# blimp_v1_-_modified.net
KiCad netlist of a schematic drawn in EAGLE
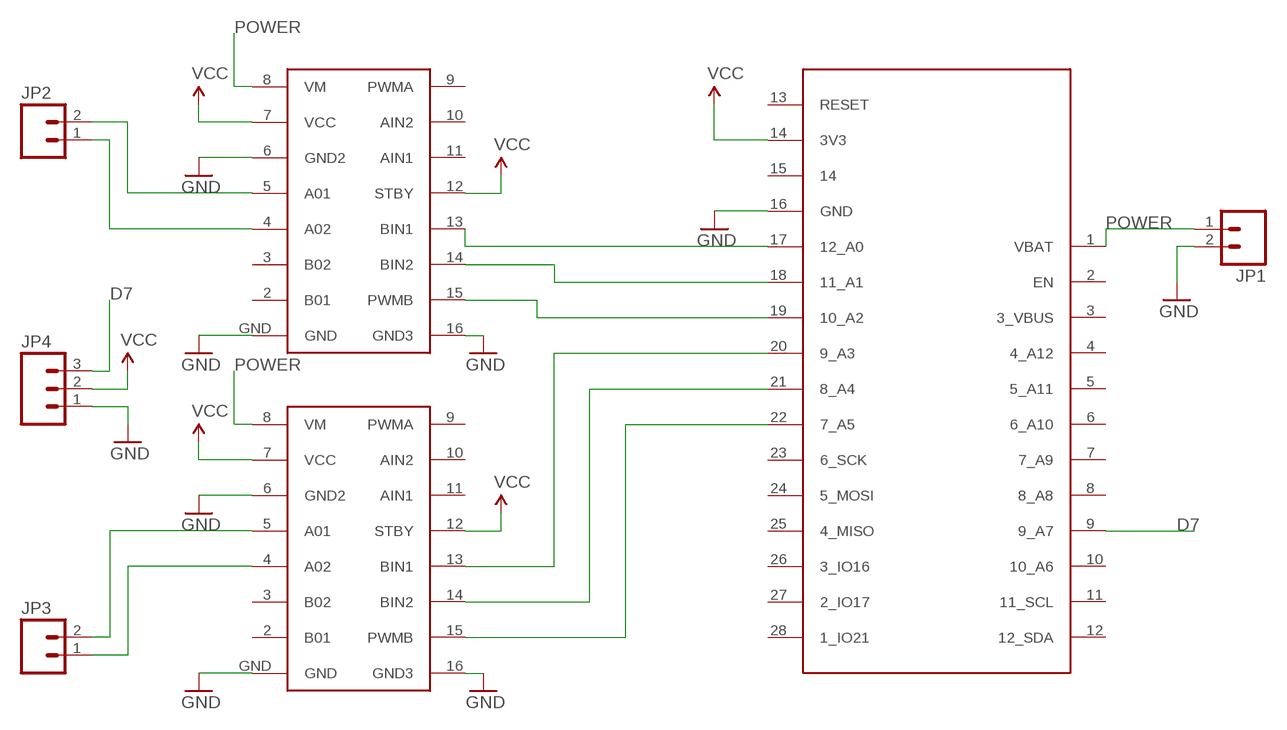
[diagram p0: schematic, sheet 1]

(export (version "E")
  (design (tool "Eeschema 10.0.6"))
  (components
    (comp (ref "JP1")
      (value "M02-JST-2MM-SMT")
      (footprint "eagle-import:JST-2-SMD")
      (libsource (lib "eagle-import") (part "M02-JST-2MM-SMT"))
    )
    (comp (ref "JP2")
      (value "M02PTH")
      (footprint "eagle-import:1X02")
      (libsource (lib "eagle-import") (part "M02PTH"))
    )
    (comp (ref "JP3")
      (value "M02PTH")
      (footprint "eagle-import:1X02")
      (libsource (lib "eagle-import") (part "M02PTH"))
    )
    (comp (ref "JP4")
      (value "M03PTH")
      (footprint "eagle-import:1X03")
      (libsource (lib "eagle-import") (part "M03PTH"))
    )
    (comp (ref "U$1")
      (value "ESP32")
      (footprint "eagle-import:ESP32")
      (libsource (lib "eagle-import") (part "ESP32"))
    )
    (comp (ref "U$2")
      (value "TB6612")
      (footprint "eagle-import:TB6612")
      (libsource (lib "eagle-import") (part "TB6612"))
    )
    (comp (ref "U$4")
      (value "TB6612")
      (footprint "eagle-import:TB6612")
      (libsource (lib "eagle-import") (part "TB6612"))
    )
  )
  (nets
    (net (code "1") (name "/D7") (class "Default")
      (node (ref "JP4") (pin "3") (pinfunction "3_3") (pintype "passive"))
      (node (ref "U$1") (pin "9") (pinfunction "9_A7_9") (pintype "bidirectional"))
    )
    (net (code "2") (name "/POWER") (class "Default")
      (node (ref "JP1") (pin "1") (pinfunction "1_1") (pintype "passive"))
      (node (ref "U$1") (pin "1") (pinfunction "VBAT_1") (pintype "bidirectional"))
      (node (ref "U$2") (pin "8") (pinfunction "VM_8") (pintype "bidirectional"))
      (node (ref "U$4") (pin "8") (pinfunction "VM_8") (pintype "bidirectional"))
    )
    (net (code "3") (name "GND") (class "Default")
      (node (ref "JP1") (pin "2") (pinfunction "2_2") (pintype "passive"))
      (node (ref "JP4") (pin "1") (pinfunction "1_1") (pintype "passive"))
      (node (ref "U$1") (pin "16") (pinfunction "GND_16") (pintype "bidirectional"))
      (node (ref "U$2") (pin "16") (pinfunction "GND3_16") (pintype "bidirectional"))
      (node (ref "U$2") (pin "6") (pinfunction "GND2_6") (pintype "bidirectional"))
      (node (ref "U$2") (pin "GND") (pinfunction "GND_GND") (pintype "bidirectional"))
      (node (ref "U$4") (pin "16") (pinfunction "GND3_16") (pintype "bidirectional"))
      (node (ref "U$4") (pin "6") (pinfunction "GND2_6") (pintype "bidirectional"))
      (node (ref "U$4") (pin "GND") (pinfunction "GND_GND") (pintype "bidirectional"))
    )
    (net (code "4") (name "Net-(U$1-7_A5)") (class "Default")
      (node (ref "U$1") (pin "22") (pinfunction "7_A5_22") (pintype "bidirectional"))
      (node (ref "U$2") (pin "15") (pinfunction "PWMB_15") (pintype "bidirectional"))
    )
    (net (code "5") (name "Net-(U$1-8_A4)") (class "Default")
      (node (ref "U$1") (pin "21") (pinfunction "8_A4_21") (pintype "bidirectional"))
      (node (ref "U$2") (pin "14") (pinfunction "BIN2_14") (pintype "bidirectional"))
    )
    (net (code "6") (name "Net-(U$1-9_A3)") (class "Default")
      (node (ref "U$1") (pin "20") (pinfunction "9_A3_20") (pintype "bidirectional"))
      (node (ref "U$2") (pin "13") (pinfunction "BIN1_13") (pintype "bidirectional"))
    )
    (net (code "7") (name "Net-(U$1-10_A2)") (class "Default")
      (node (ref "U$1") (pin "19") (pinfunction "10_A2_19") (pintype "bidirectional"))
      (node (ref "U$4") (pin "15") (pinfunction "PWMB_15") (pintype "bidirectional"))
    )
    (net (code "8") (name "Net-(U$1-11_A1)") (class "Default")
      (node (ref "U$1") (pin "18") (pinfunction "11_A1_18") (pintype "bidirectional"))
      (node (ref "U$4") (pin "14") (pinfunction "BIN2_14") (pintype "bidirectional"))
    )
    (net (code "9") (name "Net-(U$1-12_A0)") (class "Default")
      (node (ref "U$1") (pin "17") (pinfunction "12_A0_17") (pintype "bidirectional"))
      (node (ref "U$4") (pin "13") (pinfunction "BIN1_13") (pintype "bidirectional"))
    )
    (net (code "10") (name "Net-(U$2-A01)") (class "Default")
      (node (ref "JP3") (pin "2") (pinfunction "2_2") (pintype "passive"))
      (node (ref "U$2") (pin "5") (pinfunction "A01_5") (pintype "bidirectional"))
    )
    (net (code "11") (name "Net-(U$2-A02)") (class "Default")
      (node (ref "JP3") (pin "1") (pinfunction "1_1") (pintype "passive"))
      (node (ref "U$2") (pin "4") (pinfunction "A02_4") (pintype "bidirectional"))
    )
    (net (code "12") (name "Net-(U$4-A01)") (class "Default")
      (node (ref "JP2") (pin "2") (pinfunction "2_2") (pintype "passive"))
      (node (ref "U$4") (pin "5") (pinfunction "A01_5") (pintype "bidirectional"))
    )
    (net (code "13") (name "Net-(U$4-A02)") (class "Default")
      (node (ref "JP2") (pin "1") (pinfunction "1_1") (pintype "passive"))
      (node (ref "U$4") (pin "4") (pinfunction "A02_4") (pintype "bidirectional"))
    )
    (net (code "14") (name "VCC") (class "Default")
      (node (ref "JP4") (pin "2") (pinfunction "2_2") (pintype "passive"))
      (node (ref "U$1") (pin "14") (pinfunction "3V3_14") (pintype "bidirectional"))
      (node (ref "U$2") (pin "12") (pinfunction "STBY_12") (pintype "bidirectional"))
      (node (ref "U$2") (pin "7") (pinfunction "VCC_7") (pintype "bidirectional"))
      (node (ref "U$4") (pin "12") (pinfunction "STBY_12") (pintype "bidirectional"))
      (node (ref "U$4") (pin "7") (pinfunction "VCC_7") (pintype "bidirectional"))
    )
    (net (code "15") (name "unconnected-(U$1-1_IO21-Pad28)") (class "Default")
      (node (ref "U$1") (pin "28") (pinfunction "1_IO21_28") (pintype "bidirectional"))
    )
    (net (code "16") (name "unconnected-(U$1-2_IO17-Pad27)") (class "Default")
      (node (ref "U$1") (pin "27") (pinfunction "2_IO17_27") (pintype "bidirectional"))
    )
    (net (code "17") (name "unconnected-(U$1-3_IO16-Pad26)") (class "Default")
      (node (ref "U$1") (pin "26") (pinfunction "3_IO16_26") (pintype "bidirectional"))
    )
    (net (code "18") (name "unconnected-(U$1-3_VBUS-Pad3)") (class "Default")
      (node (ref "U$1") (pin "3") (pinfunction "3_VBUS_3") (pintype "bidirectional"))
    )
    (net (code "19") (name "unconnected-(U$1-4_A12-Pad4)") (class "Default")
      (node (ref "U$1") (pin "4") (pinfunction "4_A12_4") (pintype "bidirectional"))
    )
    (net (code "20") (name "unconnected-(U$1-4_MISO-Pad25)") (class "Default")
      (node (ref "U$1") (pin "25") (pinfunction "4_MISO_25") (pintype "bidirectional"))
    )
    (net (code "21") (name "unconnected-(U$1-5_A11-Pad5)") (class "Default")
      (node (ref "U$1") (pin "5") (pinfunction "5_A11_5") (pintype "bidirectional"))
    )
    (net (code "22") (name "unconnected-(U$1-5_MOSI-Pad24)") (class "Default")
      (node (ref "U$1") (pin "24") (pinfunction "5_MOSI_24") (pintype "bidirectional"))
    )
    (net (code "23") (name "unconnected-(U$1-6_A10-Pad6)") (class "Default")
      (node (ref "U$1") (pin "6") (pinfunction "6_A10_6") (pintype "bidirectional"))
    )
    (net (code "24") (name "unconnected-(U$1-6_SCK-Pad23)") (class "Default")
      (node (ref "U$1") (pin "23") (pinfunction "6_SCK_23") (pintype "bidirectional"))
    )
    (net (code "25") (name "unconnected-(U$1-7_A9-Pad7)") (class "Default")
      (node (ref "U$1") (pin "7") (pinfunction "7_A9_7") (pintype "bidirectional"))
    )
    (net (code "26") (name "unconnected-(U$1-8_A8-Pad8)") (class "Default")
      (node (ref "U$1") (pin "8") (pinfunction "8_A8_8") (pintype "bidirectional"))
    )
    (net (code "27") (name "unconnected-(U$1-10_A6-Pad10)") (class "Default")
      (node (ref "U$1") (pin "10") (pinfunction "10_A6_10") (pintype "bidirectional"))
    )
    (net (code "28") (name "unconnected-(U$1-11_SCL-Pad11)") (class "Default")
      (node (ref "U$1") (pin "11") (pinfunction "11_SCL_11") (pintype "bidirectional"))
    )
    (net (code "29") (name "unconnected-(U$1-12_SDA-Pad12)") (class "Default")
      (node (ref "U$1") (pin "12") (pinfunction "12_SDA_12") (pintype "bidirectional"))
    )
    (net (code "30") (name "unconnected-(U$1-14-Pad15)") (class "Default")
      (node (ref "U$1") (pin "15") (pinfunction "14_15") (pintype "bidirectional"))
    )
    (net (code "31") (name "unconnected-(U$1-EN-Pad2)") (class "Default")
      (node (ref "U$1") (pin "2") (pinfunction "EN_2") (pintype "bidirectional"))
    )
    (net (code "32") (name "unconnected-(U$1-RESET-Pad13)") (class "Default")
      (node (ref "U$1") (pin "13") (pinfunction "RESET_13") (pintype "bidirectional"))
    )
    (net (code "33") (name "unconnected-(U$2-AIN1-Pad11)") (class "Default")
      (node (ref "U$2") (pin "11") (pinfunction "AIN1_11") (pintype "bidirectional"))
    )
    (net (code "34") (name "unconnected-(U$2-AIN2-Pad10)") (class "Default")
      (node (ref "U$2") (pin "10") (pinfunction "AIN2_10") (pintype "bidirectional"))
    )
    (net (code "35") (name "unconnected-(U$2-B01-Pad2)") (class "Default")
      (node (ref "U$2") (pin "2") (pinfunction "B01_2") (pintype "bidirectional"))
    )
    (net (code "36") (name "unconnected-(U$2-B02-Pad3)") (class "Default")
      (node (ref "U$2") (pin "3") (pinfunction "B02_3") (pintype "bidirectional"))
    )
    (net (code "37") (name "unconnected-(U$2-PWMA-Pad9)") (class "Default")
      (node (ref "U$2") (pin "9") (pinfunction "PWMA_9") (pintype "bidirectional"))
    )
    (net (code "38") (name "unconnected-(U$4-AIN1-Pad11)") (class "Default")
      (node (ref "U$4") (pin "11") (pinfunction "AIN1_11") (pintype "bidirectional"))
    )
    (net (code "39") (name "unconnected-(U$4-AIN2-Pad10)") (class "Default")
      (node (ref "U$4") (pin "10") (pinfunction "AIN2_10") (pintype "bidirectional"))
    )
    (net (code "40") (name "unconnected-(U$4-B01-Pad2)") (class "Default")
      (node (ref "U$4") (pin "2") (pinfunction "B01_2") (pintype "bidirectional"))
    )
    (net (code "41") (name "unconnected-(U$4-B02-Pad3)") (class "Default")
      (node (ref "U$4") (pin "3") (pinfunction "B02_3") (pintype "bidirectional"))
    )
    (net (code "42") (name "unconnected-(U$4-PWMA-Pad9)") (class "Default")
      (node (ref "U$4") (pin "9") (pinfunction "PWMA_9") (pintype "bidirectional"))
    )
  )
)
